# Polivator.net
KiCad netlist of a schematic drawn in EAGLE
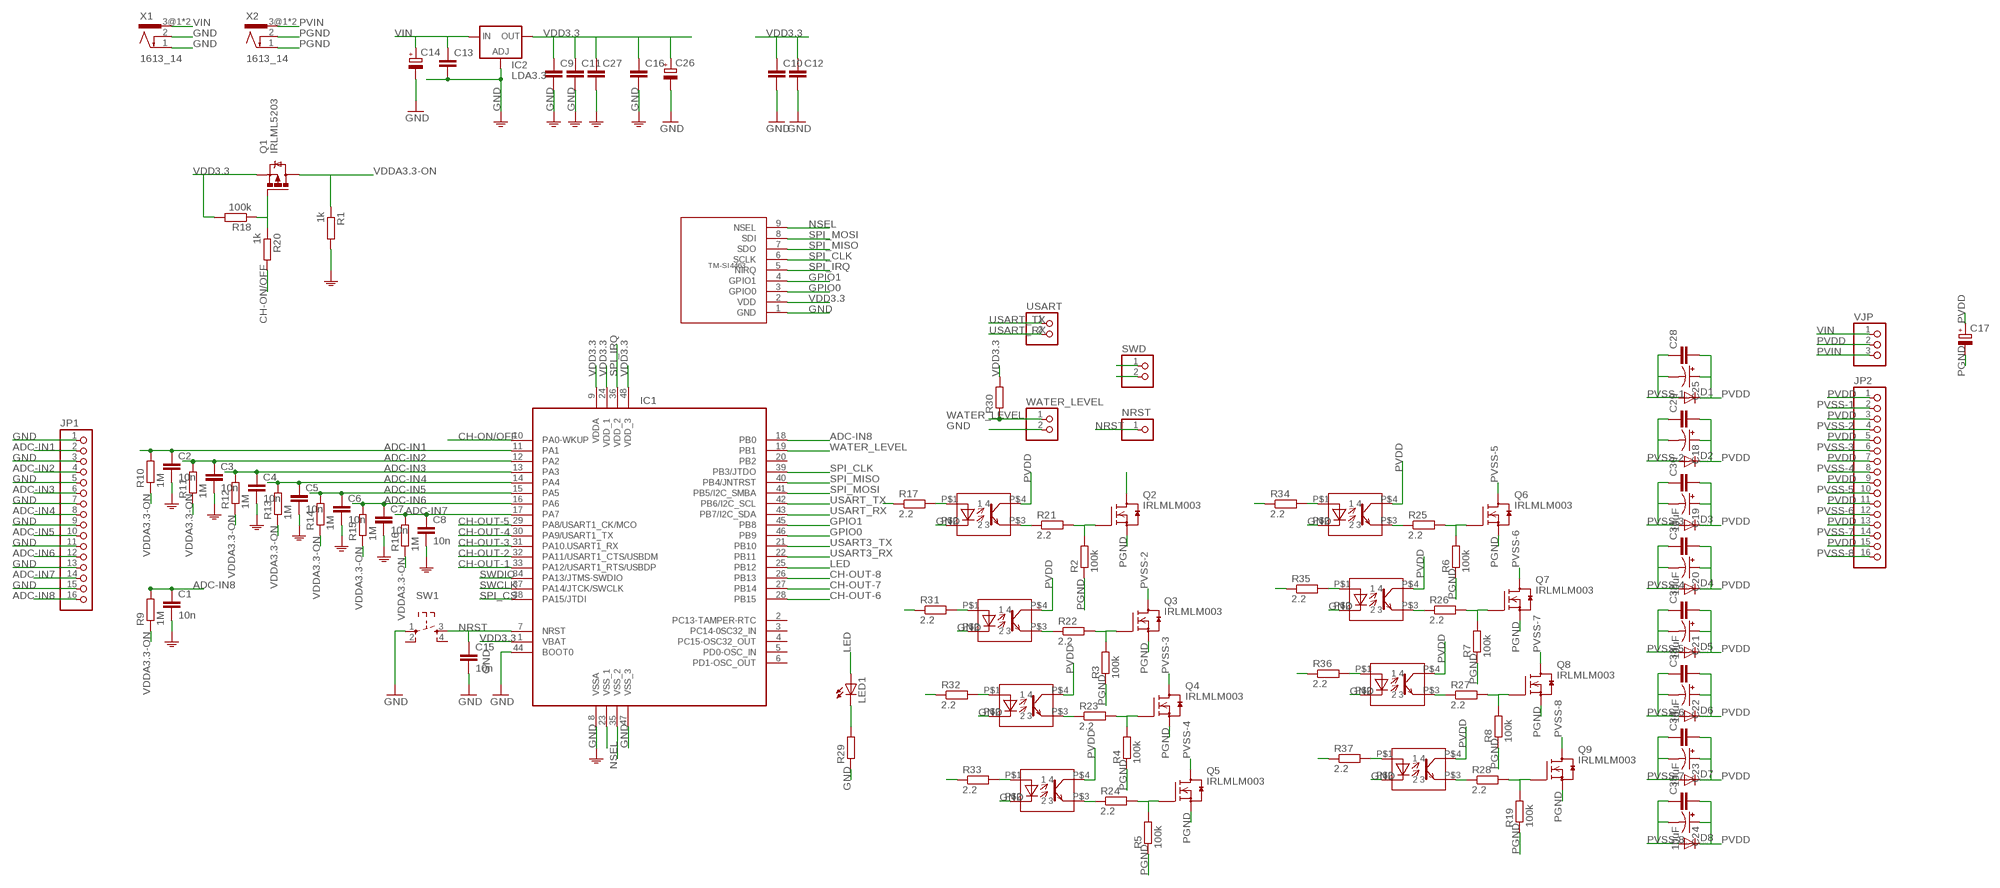
[diagram p0: schematic, sheet 1]

(export (version "E")
  (design (tool "Eeschema 10.0.6"))
  (components
    (comp (ref "C1")
      (value "10n")
      (footprint "eagle-import:C0805")
      (libsource (lib "eagle-import") (part "C-EUC0805"))
    )
    (comp (ref "C2")
      (value "10n")
      (footprint "eagle-import:C0805")
      (libsource (lib "eagle-import") (part "C-EUC0805"))
    )
    (comp (ref "C3")
      (value "10n")
      (footprint "eagle-import:C0805")
      (libsource (lib "eagle-import") (part "C-EUC0805"))
    )
    (comp (ref "C4")
      (value "10n")
      (footprint "eagle-import:C0805")
      (libsource (lib "eagle-import") (part "C-EUC0805"))
    )
    (comp (ref "C5")
      (value "10n")
      (footprint "eagle-import:C0805")
      (libsource (lib "eagle-import") (part "C-EUC0805"))
    )
    (comp (ref "C6")
      (value "10n")
      (footprint "eagle-import:C0805")
      (libsource (lib "eagle-import") (part "C-EUC0805"))
    )
    (comp (ref "C7")
      (value "10n")
      (footprint "eagle-import:C0805")
      (libsource (lib "eagle-import") (part "C-EUC0805"))
    )
    (comp (ref "C8")
      (value "10n")
      (footprint "eagle-import:C0805")
      (libsource (lib "eagle-import") (part "C-EUC0805"))
    )
    (comp (ref "C9")
      (value "C-EUC3216")
      (footprint "eagle-import:C3216")
      (libsource (lib "eagle-import") (part "C-EUC3216"))
    )
    (comp (ref "C10")
      (value "C-EUC3216")
      (footprint "eagle-import:C3216")
      (libsource (lib "eagle-import") (part "C-EUC3216"))
    )
    (comp (ref "C11")
      (value "C-EUC0805")
      (footprint "eagle-import:C0805")
      (libsource (lib "eagle-import") (part "C-EUC0805"))
    )
    (comp (ref "C12")
      (value "C-EUC0805")
      (footprint "eagle-import:C0805")
      (libsource (lib "eagle-import") (part "C-EUC0805"))
    )
    (comp (ref "C13")
      (value "C-EUC1808")
      (footprint "eagle-import:C1808")
      (libsource (lib "eagle-import") (part "C-EUC1808"))
    )
    (comp (ref "C14")
      (value "CPOL-EUE2.5-5")
      (footprint "eagle-import:E2,5-5")
      (libsource (lib "eagle-import") (part "CPOL-EUE2.5-5"))
    )
    (comp (ref "C15")
      (value "10n")
      (footprint "eagle-import:C0805")
      (libsource (lib "eagle-import") (part "C-EUC0805"))
    )
    (comp (ref "C16")
      (value "C-EUC0805")
      (footprint "eagle-import:C0805")
      (libsource (lib "eagle-import") (part "C-EUC0805"))
    )
    (comp (ref "C17")
      (value "CPOL-EUE2.5-6")
      (footprint "eagle-import:E2,5-6")
      (libsource (lib "eagle-import") (part "CPOL-EUE2.5-6"))
    )
    (comp (ref "C18")
      (value "CAP_POL1206")
      (footprint "eagle-import:EIA3216")
      (libsource (lib "eagle-import") (part "CAP_POL1206"))
    )
    (comp (ref "C19")
      (value "10uF")
      (footprint "eagle-import:EIA3216")
      (libsource (lib "eagle-import") (part "10UF-16V-10%(TANT)"))
    )
    (comp (ref "C20")
      (value "10uF")
      (footprint "eagle-import:EIA3216")
      (libsource (lib "eagle-import") (part "10UF-16V-10%(TANT)"))
    )
    (comp (ref "C21")
      (value "10uF")
      (footprint "eagle-import:EIA3216")
      (libsource (lib "eagle-import") (part "10UF-16V-10%(TANT)"))
    )
    (comp (ref "C22")
      (value "10uF")
      (footprint "eagle-import:EIA3216")
      (libsource (lib "eagle-import") (part "10UF-16V-10%(TANT)"))
    )
    (comp (ref "C23")
      (value "10uF")
      (footprint "eagle-import:EIA3216")
      (libsource (lib "eagle-import") (part "10UF-16V-10%(TANT)"))
    )
    (comp (ref "C24")
      (value "10uF")
      (footprint "eagle-import:EIA3216")
      (libsource (lib "eagle-import") (part "10UF-16V-10%(TANT)"))
    )
    (comp (ref "C25")
      (value "CAP_POL1206")
      (footprint "eagle-import:EIA3216")
      (libsource (lib "eagle-import") (part "CAP_POL1206"))
    )
    (comp (ref "C26")
      (value "CPOL-EUE2.5-5")
      (footprint "eagle-import:E2,5-5")
      (libsource (lib "eagle-import") (part "CPOL-EUE2.5-5"))
    )
    (comp (ref "C27")
      (value "C-EUC0805")
      (footprint "eagle-import:C0805")
      (libsource (lib "eagle-import") (part "C-EUC0805"))
    )
    (comp (ref "C28")
      (value "C-EUC0805")
      (footprint "eagle-import:C0805")
      (libsource (lib "eagle-import") (part "C-EUC0805"))
    )
    (comp (ref "C29")
      (value "C-EUC0805")
      (footprint "eagle-import:C0805")
      (libsource (lib "eagle-import") (part "C-EUC0805"))
    )
    (comp (ref "C30")
      (value "C-EUC0805")
      (footprint "eagle-import:C0805")
      (libsource (lib "eagle-import") (part "C-EUC0805"))
    )
    (comp (ref "C31")
      (value "C-EUC0805")
      (footprint "eagle-import:C0805")
      (libsource (lib "eagle-import") (part "C-EUC0805"))
    )
    (comp (ref "C32")
      (value "C-EUC0805")
      (footprint "eagle-import:C0805")
      (libsource (lib "eagle-import") (part "C-EUC0805"))
    )
    (comp (ref "C33")
      (value "C-EUC0805")
      (footprint "eagle-import:C0805")
      (libsource (lib "eagle-import") (part "C-EUC0805"))
    )
    (comp (ref "C34")
      (value "C-EUC0805")
      (footprint "eagle-import:C0805")
      (libsource (lib "eagle-import") (part "C-EUC0805"))
    )
    (comp (ref "C35")
      (value "C-EUC0805")
      (footprint "eagle-import:C0805")
      (libsource (lib "eagle-import") (part "C-EUC0805"))
    )
    (comp (ref "D1")
      (value "DIODE-SOD80C")
      (footprint "eagle-import:SOD80C")
      (libsource (lib "eagle-import") (part "DIODE-SOD80C"))
    )
    (comp (ref "D2")
      (value "DIODE-SOD80C")
      (footprint "eagle-import:SOD80C")
      (libsource (lib "eagle-import") (part "DIODE-SOD80C"))
    )
    (comp (ref "D3")
      (value "DIODE-SOD80C")
      (footprint "eagle-import:SOD80C")
      (libsource (lib "eagle-import") (part "DIODE-SOD80C"))
    )
    (comp (ref "D4")
      (value "DIODE-SOD80C")
      (footprint "eagle-import:SOD80C")
      (libsource (lib "eagle-import") (part "DIODE-SOD80C"))
    )
    (comp (ref "D5")
      (value "DIODE-SOD80C")
      (footprint "eagle-import:SOD80C")
      (libsource (lib "eagle-import") (part "DIODE-SOD80C"))
    )
    (comp (ref "D6")
      (value "DIODE-SOD80C")
      (footprint "eagle-import:SOD80C")
      (libsource (lib "eagle-import") (part "DIODE-SOD80C"))
    )
    (comp (ref "D7")
      (value "DIODE-SOD80C")
      (footprint "eagle-import:SOD80C")
      (libsource (lib "eagle-import") (part "DIODE-SOD80C"))
    )
    (comp (ref "D8")
      (value "DIODE-SOD80C")
      (footprint "eagle-import:SOD80C")
      (libsource (lib "eagle-import") (part "DIODE-SOD80C"))
    )
    (comp (ref "IC1")
      (value "IC_UC_STM32")
      (footprint "eagle-import:LQFP48")
      (libsource (lib "eagle-import") (part "IC_UC_STM32"))
    )
    (comp (ref "IC2")
      (value "LDA3.3")
      (footprint "eagle-import:SOT223")
      (libsource (lib "eagle-import") (part "LD117A?STR"))
    )
    (comp (ref "JP1")
      (value "PINHD-1X16")
      (footprint "eagle-import:1X16")
      (libsource (lib "eagle-import") (part "PINHD-1X16"))
    )
    (comp (ref "JP2")
      (value "PINHD-1X16")
      (footprint "eagle-import:1X16")
      (libsource (lib "eagle-import") (part "PINHD-1X16"))
    )
    (comp (ref "LED1")
      (value "LEDCHIPLED_0805")
      (footprint "eagle-import:CHIPLED_0805")
      (libsource (lib "eagle-import") (part "LEDCHIPLED_0805"))
    )
    (comp (ref "NRST")
      (value "PINHD-1X1")
      (footprint "eagle-import:1X01")
      (libsource (lib "eagle-import") (part "PINHD-1X1"))
    )
    (comp (ref "Q1")
      (value "IRLML5203")
      (footprint "eagle-import:MICRO3")
      (libsource (lib "eagle-import") (part "IRLML5203"))
    )
    (comp (ref "Q2")
      (value "IRLMLM003")
      (footprint "eagle-import:SOT23")
      (libsource (lib "eagle-import") (part "BSS138"))
    )
    (comp (ref "Q3")
      (value "IRLMLM003")
      (footprint "eagle-import:SOT23")
      (libsource (lib "eagle-import") (part "BSS138"))
    )
    (comp (ref "Q4")
      (value "IRLMLM003")
      (footprint "eagle-import:SOT23")
      (libsource (lib "eagle-import") (part "BSS138"))
    )
    (comp (ref "Q5")
      (value "IRLMLM003")
      (footprint "eagle-import:SOT23")
      (libsource (lib "eagle-import") (part "BSS138"))
    )
    (comp (ref "Q6")
      (value "IRLMLM003")
      (footprint "eagle-import:SOT23")
      (libsource (lib "eagle-import") (part "BSS138"))
    )
    (comp (ref "Q7")
      (value "IRLMLM003")
      (footprint "eagle-import:SOT23")
      (libsource (lib "eagle-import") (part "BSS138"))
    )
    (comp (ref "Q8")
      (value "IRLMLM003")
      (footprint "eagle-import:SOT23")
      (libsource (lib "eagle-import") (part "BSS138"))
    )
    (comp (ref "Q9")
      (value "IRLMLM003")
      (footprint "eagle-import:SOT23")
      (libsource (lib "eagle-import") (part "BSS138"))
    )
    (comp (ref "R1")
      (value "1k")
      (footprint "eagle-import:R0805")
      (libsource (lib "eagle-import") (part "R-EU_R0805"))
    )
    (comp (ref "R2")
      (value "100k")
      (footprint "eagle-import:R0805")
      (libsource (lib "eagle-import") (part "R-EU_R0805"))
    )
    (comp (ref "R3")
      (value "100k")
      (footprint "eagle-import:R0805")
      (libsource (lib "eagle-import") (part "R-EU_R0805"))
    )
    (comp (ref "R4")
      (value "100k")
      (footprint "eagle-import:R0805")
      (libsource (lib "eagle-import") (part "R-EU_R0805"))
    )
    (comp (ref "R5")
      (value "100k")
      (footprint "eagle-import:R0805")
      (libsource (lib "eagle-import") (part "R-EU_R0805"))
    )
    (comp (ref "R6")
      (value "100k")
      (footprint "eagle-import:R0805")
      (libsource (lib "eagle-import") (part "R-EU_R0805"))
    )
    (comp (ref "R7")
      (value "100k")
      (footprint "eagle-import:R0805")
      (libsource (lib "eagle-import") (part "R-EU_R0805"))
    )
    (comp (ref "R8")
      (value "100k")
      (footprint "eagle-import:R0805")
      (libsource (lib "eagle-import") (part "R-EU_R0805"))
    )
    (comp (ref "R9")
      (value "1M")
      (footprint "eagle-import:R0805")
      (libsource (lib "eagle-import") (part "R-EU_R0805"))
    )
    (comp (ref "R10")
      (value "1M")
      (footprint "eagle-import:R0805")
      (libsource (lib "eagle-import") (part "R-EU_R0805"))
    )
    (comp (ref "R11")
      (value "1M")
      (footprint "eagle-import:R0805")
      (libsource (lib "eagle-import") (part "R-EU_R0805"))
    )
    (comp (ref "R12")
      (value "1M")
      (footprint "eagle-import:R0805")
      (libsource (lib "eagle-import") (part "R-EU_R0805"))
    )
    (comp (ref "R13")
      (value "1M")
      (footprint "eagle-import:R0805")
      (libsource (lib "eagle-import") (part "R-EU_R0805"))
    )
    (comp (ref "R14")
      (value "1M")
      (footprint "eagle-import:R0805")
      (libsource (lib "eagle-import") (part "R-EU_R0805"))
    )
    (comp (ref "R15")
      (value "1M")
      (footprint "eagle-import:R0805")
      (libsource (lib "eagle-import") (part "R-EU_R0805"))
    )
    (comp (ref "R16")
      (value "1M")
      (footprint "eagle-import:R0805")
      (libsource (lib "eagle-import") (part "R-EU_R0805"))
    )
    (comp (ref "R17")
      (value "2.2")
      (footprint "eagle-import:R0805")
      (libsource (lib "eagle-import") (part "R-EU_R0805"))
    )
    (comp (ref "R18")
      (value "100k")
      (footprint "eagle-import:R0805")
      (libsource (lib "eagle-import") (part "R-EU_R0805"))
    )
    (comp (ref "R19")
      (value "100k")
      (footprint "eagle-import:R0805")
      (libsource (lib "eagle-import") (part "R-EU_R0805"))
    )
    (comp (ref "R20")
      (value "1k")
      (footprint "eagle-import:R0805")
      (libsource (lib "eagle-import") (part "R-EU_R0805"))
    )
    (comp (ref "R21")
      (value "2.2")
      (footprint "eagle-import:R0805")
      (libsource (lib "eagle-import") (part "R-EU_R0805"))
    )
    (comp (ref "R22")
      (value "2.2")
      (footprint "eagle-import:R0805")
      (libsource (lib "eagle-import") (part "R-EU_R0805"))
    )
    (comp (ref "R23")
      (value "2.2")
      (footprint "eagle-import:R0805")
      (libsource (lib "eagle-import") (part "R-EU_R0805"))
    )
    (comp (ref "R24")
      (value "2.2")
      (footprint "eagle-import:R0805")
      (libsource (lib "eagle-import") (part "R-EU_R0805"))
    )
    (comp (ref "R25")
      (value "2.2")
      (footprint "eagle-import:R0805")
      (libsource (lib "eagle-import") (part "R-EU_R0805"))
    )
    (comp (ref "R26")
      (value "2.2")
      (footprint "eagle-import:R0805")
      (libsource (lib "eagle-import") (part "R-EU_R0805"))
    )
    (comp (ref "R27")
      (value "2.2")
      (footprint "eagle-import:R0805")
      (libsource (lib "eagle-import") (part "R-EU_R0805"))
    )
    (comp (ref "R28")
      (value "2.2")
      (footprint "eagle-import:R0805")
      (libsource (lib "eagle-import") (part "R-EU_R0805"))
    )
    (comp (ref "R29")
      (value "R-EU_R0805")
      (footprint "eagle-import:R0805")
      (libsource (lib "eagle-import") (part "R-EU_R0805"))
    )
    (comp (ref "R30")
      (value "R-EU_R0805")
      (footprint "eagle-import:R0805")
      (libsource (lib "eagle-import") (part "R-EU_R0805"))
    )
    (comp (ref "R31")
      (value "2.2")
      (footprint "eagle-import:R0805")
      (libsource (lib "eagle-import") (part "R-EU_R0805"))
    )
    (comp (ref "R32")
      (value "2.2")
      (footprint "eagle-import:R0805")
      (libsource (lib "eagle-import") (part "R-EU_R0805"))
    )
    (comp (ref "R33")
      (value "2.2")
      (footprint "eagle-import:R0805")
      (libsource (lib "eagle-import") (part "R-EU_R0805"))
    )
    (comp (ref "R34")
      (value "2.2")
      (footprint "eagle-import:R0805")
      (libsource (lib "eagle-import") (part "R-EU_R0805"))
    )
    (comp (ref "R35")
      (value "2.2")
      (footprint "eagle-import:R0805")
      (libsource (lib "eagle-import") (part "R-EU_R0805"))
    )
    (comp (ref "R36")
      (value "2.2")
      (footprint "eagle-import:R0805")
      (libsource (lib "eagle-import") (part "R-EU_R0805"))
    )
    (comp (ref "R37")
      (value "2.2")
      (footprint "eagle-import:R0805")
      (libsource (lib "eagle-import") (part "R-EU_R0805"))
    )
    (comp (ref "SW1")
      (value "SW_TACT_4P")
      (footprint "eagle-import:SW_TACT_SMALL")
      (libsource (lib "eagle-import") (part "SW_TACT_4P"))
    )
    (comp (ref "SWD")
      (value "PINHD-1X2")
      (footprint "eagle-import:1X02")
      (libsource (lib "eagle-import") (part "PINHD-1X2"))
    )
    (comp (ref "U$8")
      (value "TM-SI4463")
      (footprint "eagle-import:TM-SI4463-SMD")
      (libsource (lib "eagle-import") (part "TM-SI4463"))
    )
    (comp (ref "U$10")
      (value "PC817-SMD")
      (footprint "eagle-import:PC817-SMD")
      (libsource (lib "eagle-import") (part "PC817-SMD"))
    )
    (comp (ref "U$11")
      (value "PC817-SMD")
      (footprint "eagle-import:PC817-SMD")
      (libsource (lib "eagle-import") (part "PC817-SMD"))
    )
    (comp (ref "U$13")
      (value "PC817-SMD")
      (footprint "eagle-import:PC817-SMD")
      (libsource (lib "eagle-import") (part "PC817-SMD"))
    )
    (comp (ref "U$16")
      (value "PC817-SMD")
      (footprint "eagle-import:PC817-SMD")
      (libsource (lib "eagle-import") (part "PC817-SMD"))
    )
    (comp (ref "U$18")
      (value "PC817-SMD")
      (footprint "eagle-import:PC817-SMD")
      (libsource (lib "eagle-import") (part "PC817-SMD"))
    )
    (comp (ref "U$20")
      (value "PC817-SMD")
      (footprint "eagle-import:PC817-SMD")
      (libsource (lib "eagle-import") (part "PC817-SMD"))
    )
    (comp (ref "U$23")
      (value "PC817-SMD")
      (footprint "eagle-import:PC817-SMD")
      (libsource (lib "eagle-import") (part "PC817-SMD"))
    )
    (comp (ref "U$24")
      (value "PC817-SMD")
      (footprint "eagle-import:PC817-SMD")
      (libsource (lib "eagle-import") (part "PC817-SMD"))
    )
    (comp (ref "USART")
      (value "PINHD-1X2")
      (footprint "eagle-import:1X02")
      (libsource (lib "eagle-import") (part "PINHD-1X2"))
    )
    (comp (ref "VJP")
      (value "PINHD-1X3")
      (footprint "eagle-import:1X03")
      (libsource (lib "eagle-import") (part "PINHD-1X3"))
    )
    (comp (ref "WATER_LEVEL")
      (value "PINHD-1X2")
      (footprint "eagle-import:1X02")
      (libsource (lib "eagle-import") (part "PINHD-1X2"))
    )
    (comp (ref "X1")
      (value "1613_14")
      (footprint "eagle-import:1613_14")
      (fields (field (name "MF") "LUMBERG") (field (name "MPN") "1613 14"))
      (libsource (lib "eagle-import") (part "1613_14"))
    )
    (comp (ref "X2")
      (value "1613_14")
      (footprint "eagle-import:1613_14")
      (fields (field (name "MF") "LUMBERG") (field (name "MPN") "1613 14"))
      (libsource (lib "eagle-import") (part "1613_14"))
    )
  )
  (nets
    (net (code "1") (name "/ADC-IN1") (class "Default")
      (node (ref "C2") (pin "1") (pinfunction "1_1") (pintype "passive"))
      (node (ref "IC1") (pin "11") (pinfunction "PA1_11") (pintype "bidirectional"))
      (node (ref "JP1") (pin "2") (pinfunction "2_2") (pintype "passive"))
      (node (ref "R10") (pin "2") (pinfunction "2_2") (pintype "passive"))
    )
    (net (code "2") (name "/ADC-IN2") (class "Default")
      (node (ref "C3") (pin "1") (pinfunction "1_1") (pintype "passive"))
      (node (ref "IC1") (pin "12") (pinfunction "PA2_12") (pintype "bidirectional"))
      (node (ref "JP1") (pin "4") (pinfunction "4_4") (pintype "passive"))
      (node (ref "R11") (pin "2") (pinfunction "2_2") (pintype "passive"))
    )
    (net (code "3") (name "/ADC-IN3") (class "Default")
      (node (ref "C4") (pin "1") (pinfunction "1_1") (pintype "passive"))
      (node (ref "IC1") (pin "13") (pinfunction "PA3_13") (pintype "bidirectional"))
      (node (ref "JP1") (pin "6") (pinfunction "6_6") (pintype "passive"))
      (node (ref "R12") (pin "2") (pinfunction "2_2") (pintype "passive"))
    )
    (net (code "4") (name "/ADC-IN4") (class "Default")
      (node (ref "C5") (pin "1") (pinfunction "1_1") (pintype "passive"))
      (node (ref "IC1") (pin "14") (pinfunction "PA4_14") (pintype "bidirectional"))
      (node (ref "JP1") (pin "8") (pinfunction "8_8") (pintype "passive"))
      (node (ref "R13") (pin "2") (pinfunction "2_2") (pintype "passive"))
    )
    (net (code "5") (name "/ADC-IN5") (class "Default")
      (node (ref "C6") (pin "1") (pinfunction "1_1") (pintype "passive"))
      (node (ref "IC1") (pin "15") (pinfunction "PA5_15") (pintype "bidirectional"))
      (node (ref "JP1") (pin "10") (pinfunction "10_10") (pintype "passive"))
      (node (ref "R14") (pin "2") (pinfunction "2_2") (pintype "passive"))
    )
    (net (code "6") (name "/ADC-IN6") (class "Default")
      (node (ref "C7") (pin "1") (pinfunction "1_1") (pintype "passive"))
      (node (ref "IC1") (pin "16") (pinfunction "PA6_16") (pintype "bidirectional"))
      (node (ref "JP1") (pin "12") (pinfunction "12_12") (pintype "passive"))
      (node (ref "R15") (pin "2") (pinfunction "2_2") (pintype "passive"))
    )
    (net (code "7") (name "/ADC-IN7") (class "Default")
      (node (ref "C8") (pin "1") (pinfunction "1_1") (pintype "passive"))
      (node (ref "IC1") (pin "17") (pinfunction "PA7_17") (pintype "bidirectional"))
      (node (ref "JP1") (pin "14") (pinfunction "14_14") (pintype "passive"))
      (node (ref "R16") (pin "2") (pinfunction "2_2") (pintype "passive"))
    )
    (net (code "8") (name "/ADC-IN8") (class "Default")
      (node (ref "C1") (pin "1") (pinfunction "1_1") (pintype "passive"))
      (node (ref "IC1") (pin "18") (pinfunction "PB0_18") (pintype "bidirectional"))
      (node (ref "JP1") (pin "16") (pinfunction "16_16") (pintype "passive"))
      (node (ref "R9") (pin "2") (pinfunction "2_2") (pintype "passive"))
    )
    (net (code "9") (name "/CH-ON{slash}OFF") (class "Default")
      (node (ref "IC1") (pin "10") (pinfunction "PA0-WKUP_10") (pintype "bidirectional"))
      (node (ref "R20") (pin "2") (pinfunction "2_2") (pintype "passive"))
    )
    (net (code "10") (name "/CH-OUT-1") (class "Default")
      (node (ref "IC1") (pin "33") (pinfunction "PA12/USART1_RTS/USBDP_33") (pintype "bidirectional"))
      (node (ref "R17") (pin "1") (pinfunction "1_1") (pintype "passive"))
    )
    (net (code "11") (name "/CH-OUT-2") (class "Default")
      (node (ref "IC1") (pin "32") (pinfunction "PA11/USART1_CTS/USBDM_32") (pintype "bidirectional"))
      (node (ref "R31") (pin "1") (pinfunction "1_1") (pintype "passive"))
    )
    (net (code "12") (name "/CH-OUT-3") (class "Default")
      (node (ref "IC1") (pin "31") (pinfunction "PA10.USART1_RX_31") (pintype "bidirectional"))
      (node (ref "R32") (pin "1") (pinfunction "1_1") (pintype "passive"))
    )
    (net (code "13") (name "/CH-OUT-4") (class "Default")
      (node (ref "IC1") (pin "30") (pinfunction "PA9/USART1_TX_30") (pintype "bidirectional"))
      (node (ref "R33") (pin "1") (pinfunction "1_1") (pintype "passive"))
    )
    (net (code "14") (name "/CH-OUT-5") (class "Default")
      (node (ref "IC1") (pin "29") (pinfunction "PA8/USART1_CK/MCO_29") (pintype "bidirectional"))
      (node (ref "R34") (pin "1") (pinfunction "1_1") (pintype "passive"))
    )
    (net (code "15") (name "/CH-OUT-6") (class "Default")
      (node (ref "IC1") (pin "28") (pinfunction "PB15_28") (pintype "bidirectional"))
      (node (ref "R35") (pin "1") (pinfunction "1_1") (pintype "passive"))
    )
    (net (code "16") (name "/CH-OUT-7") (class "Default")
      (node (ref "IC1") (pin "27") (pinfunction "PB14_27") (pintype "bidirectional"))
      (node (ref "R36") (pin "1") (pinfunction "1_1") (pintype "passive"))
    )
    (net (code "17") (name "/CH-OUT-8") (class "Default")
      (node (ref "IC1") (pin "26") (pinfunction "PB13_26") (pintype "bidirectional"))
      (node (ref "R37") (pin "1") (pinfunction "1_1") (pintype "passive"))
    )
    (net (code "18") (name "/GPIO0") (class "Default")
      (node (ref "IC1") (pin "46") (pinfunction "PB9_46") (pintype "bidirectional"))
      (node (ref "U$8") (pin "3") (pinfunction "GPIO0_3") (pintype "bidirectional"))
    )
    (net (code "19") (name "/GPIO1") (class "Default")
      (node (ref "IC1") (pin "45") (pinfunction "PB8_45") (pintype "bidirectional"))
      (node (ref "U$8") (pin "4") (pinfunction "GPIO1_4") (pintype "bidirectional"))
    )
    (net (code "20") (name "/LED") (class "Default")
      (node (ref "IC1") (pin "25") (pinfunction "PB12_25") (pintype "bidirectional"))
      (node (ref "LED1") (pin "A") (pinfunction "A_A") (pintype "passive"))
    )
    (net (code "21") (name "/NRST") (class "Default")
      (node (ref "C15") (pin "1") (pinfunction "1_1") (pintype "passive"))
      (node (ref "IC1") (pin "7") (pinfunction "NRST_7") (pintype "bidirectional"))
      (node (ref "NRST") (pin "1") (pinfunction "1_1") (pintype "passive"))
      (node (ref "SW1") (pin "3") (pinfunction "3_3") (pintype "passive"))
    )
    (net (code "22") (name "/NSEL") (class "Default")
      (node (ref "IC1") (pin "35") (pinfunction "VSS_2_35") (pintype "power_in"))
      (node (ref "U$8") (pin "9") (pinfunction "NSEL_9") (pintype "bidirectional"))
    )
    (net (code "23") (name "/PGND") (class "Default")
      (node (ref "C17") (pin "-") (pinfunction "-_-") (pintype "passive"))
      (node (ref "Q2") (pin "2") (pinfunction "S_2") (pintype "passive"))
      (node (ref "Q3") (pin "2") (pinfunction "S_2") (pintype "passive"))
      (node (ref "Q4") (pin "2") (pinfunction "S_2") (pintype "passive"))
      (node (ref "Q5") (pin "2") (pinfunction "S_2") (pintype "passive"))
      (node (ref "Q6") (pin "2") (pinfunction "S_2") (pintype "passive"))
      (node (ref "Q7") (pin "2") (pinfunction "S_2") (pintype "passive"))
      (node (ref "Q8") (pin "2") (pinfunction "S_2") (pintype "passive"))
      (node (ref "Q9") (pin "2") (pinfunction "S_2") (pintype "passive"))
      (node (ref "R19") (pin "1") (pinfunction "1_1") (pintype "passive"))
      (node (ref "R2") (pin "1") (pinfunction "1_1") (pintype "passive"))
      (node (ref "R3") (pin "1") (pinfunction "1_1") (pintype "passive"))
      (node (ref "R4") (pin "1") (pinfunction "1_1") (pintype "passive"))
      (node (ref "R5") (pin "1") (pinfunction "1_1") (pintype "passive"))
      (node (ref "R6") (pin "1") (pinfunction "1_1") (pintype "passive"))
      (node (ref "R7") (pin "1") (pinfunction "1_1") (pintype "passive"))
      (node (ref "R8") (pin "1") (pinfunction "1_1") (pintype "passive"))
      (node (ref "X2") (pin "1") (pinfunction "1_1") (pintype "passive"))
      (node (ref "X2") (pin "2") (pinfunction "2_2") (pintype "passive"))
    )
    (net (code "24") (name "/PVDD") (class "Default")
      (node (ref "C17") (pin "+") (pinfunction "+_+") (pintype "passive"))
      (node (ref "C18") (pin "A") (pinfunction "+_A") (pintype "passive"))
      (node (ref "C19") (pin "A") (pinfunction "+_A") (pintype "passive"))
      (node (ref "C20") (pin "A") (pinfunction "+_A") (pintype "passive"))
      (node (ref "C21") (pin "A") (pinfunction "+_A") (pintype "passive"))
      (node (ref "C22") (pin "A") (pinfunction "+_A") (pintype "passive"))
      (node (ref "C23") (pin "A") (pinfunction "+_A") (pintype "passive"))
      (node (ref "C24") (pin "A") (pinfunction "+_A") (pintype "passive"))
      (node (ref "C25") (pin "A") (pinfunction "+_A") (pintype "passive"))
      (node (ref "C28") (pin "2") (pinfunction "2_2") (pintype "passive"))
      (node (ref "C29") (pin "2") (pinfunction "2_2") (pintype "passive"))
      (node (ref "C30") (pin "2") (pinfunction "2_2") (pintype "passive"))
      (node (ref "C31") (pin "2") (pinfunction "2_2") (pintype "passive"))
      (node (ref "C32") (pin "2") (pinfunction "2_2") (pintype "passive"))
      (node (ref "C33") (pin "2") (pinfunction "2_2") (pintype "passive"))
      (node (ref "C34") (pin "2") (pinfunction "2_2") (pintype "passive"))
      (node (ref "C35") (pin "2") (pinfunction "2_2") (pintype "passive"))
      (node (ref "D1") (pin "C") (pinfunction "C_C") (pintype "passive"))
      (node (ref "D2") (pin "C") (pinfunction "C_C") (pintype "passive"))
      (node (ref "D3") (pin "C") (pinfunction "C_C") (pintype "passive"))
      (node (ref "D4") (pin "C") (pinfunction "C_C") (pintype "passive"))
      (node (ref "D5") (pin "C") (pinfunction "C_C") (pintype "passive"))
      (node (ref "D6") (pin "C") (pinfunction "C_C") (pintype "passive"))
      (node (ref "D7") (pin "C") (pinfunction "C_C") (pintype "passive"))
      (node (ref "D8") (pin "C") (pinfunction "C_C") (pintype "passive"))
      (node (ref "JP2") (pin "1") (pinfunction "1_1") (pintype "passive"))
      (node (ref "JP2") (pin "11") (pinfunction "11_11") (pintype "passive"))
      (node (ref "JP2") (pin "13") (pinfunction "13_13") (pintype "passive"))
      (node (ref "JP2") (pin "15") (pinfunction "15_15") (pintype "passive"))
      (node (ref "JP2") (pin "3") (pinfunction "3_3") (pintype "passive"))
      (node (ref "JP2") (pin "5") (pinfunction "5_5") (pintype "passive"))
      (node (ref "JP2") (pin "7") (pinfunction "7_7") (pintype "passive"))
      (node (ref "JP2") (pin "9") (pinfunction "9_9") (pintype "passive"))
      (node (ref "U$10") (pin "P$4") (pinfunction "4_P$4") (pintype "bidirectional"))
      (node (ref "U$11") (pin "P$4") (pinfunction "4_P$4") (pintype "bidirectional"))
      (node (ref "U$13") (pin "P$4") (pinfunction "4_P$4") (pintype "bidirectional"))
      (node (ref "U$16") (pin "P$4") (pinfunction "4_P$4") (pintype "bidirectional"))
      (node (ref "U$18") (pin "P$4") (pinfunction "4_P$4") (pintype "bidirectional"))
      (node (ref "U$20") (pin "P$4") (pinfunction "4_P$4") (pintype "bidirectional"))
      (node (ref "U$23") (pin "P$4") (pinfunction "4_P$4") (pintype "bidirectional"))
      (node (ref "U$24") (pin "P$4") (pinfunction "4_P$4") (pintype "bidirectional"))
      (node (ref "VJP") (pin "2") (pinfunction "2_2") (pintype "passive"))
    )
    (net (code "25") (name "/PVIN") (class "Default")
      (node (ref "VJP") (pin "3") (pinfunction "3_3") (pintype "passive"))
      (node (ref "X2") (pin "3@1") (pinfunction "3_3@1") (pintype "passive"))
      (node (ref "X2") (pin "3@2") (pinfunction "3_3@2") (pintype "passive"))
    )
    (net (code "26") (name "/PVSS-1") (class "Default")
      (node (ref "C25") (pin "C") (pinfunction "-_C") (pintype "passive"))
      (node (ref "C28") (pin "1") (pinfunction "1_1") (pintype "passive"))
      (node (ref "D1") (pin "A") (pinfunction "A_A") (pintype "passive"))
      (node (ref "JP2") (pin "2") (pinfunction "2_2") (pintype "passive"))
      (node (ref "Q2") (pin "3") (pinfunction "D_3") (pintype "passive"))
    )
    (net (code "27") (name "/PVSS-2") (class "Default")
      (node (ref "C18") (pin "C") (pinfunction "-_C") (pintype "passive"))
      (node (ref "C29") (pin "1") (pinfunction "1_1") (pintype "passive"))
      (node (ref "D2") (pin "A") (pinfunction "A_A") (pintype "passive"))
      (node (ref "JP2") (pin "4") (pinfunction "4_4") (pintype "passive"))
      (node (ref "Q3") (pin "3") (pinfunction "D_3") (pintype "passive"))
    )
    (net (code "28") (name "/PVSS-3") (class "Default")
      (node (ref "C19") (pin "C") (pinfunction "-_C") (pintype "passive"))
      (node (ref "C30") (pin "1") (pinfunction "1_1") (pintype "passive"))
      (node (ref "D3") (pin "A") (pinfunction "A_A") (pintype "passive"))
      (node (ref "JP2") (pin "6") (pinfunction "6_6") (pintype "passive"))
      (node (ref "Q4") (pin "3") (pinfunction "D_3") (pintype "passive"))
    )
    (net (code "29") (name "/PVSS-4") (class "Default")
      (node (ref "C20") (pin "C") (pinfunction "-_C") (pintype "passive"))
      (node (ref "C31") (pin "1") (pinfunction "1_1") (pintype "passive"))
      (node (ref "D4") (pin "A") (pinfunction "A_A") (pintype "passive"))
      (node (ref "JP2") (pin "8") (pinfunction "8_8") (pintype "passive"))
      (node (ref "Q5") (pin "3") (pinfunction "D_3") (pintype "passive"))
    )
    (net (code "30") (name "/PVSS-5") (class "Default")
      (node (ref "C21") (pin "C") (pinfunction "-_C") (pintype "passive"))
      (node (ref "C32") (pin "1") (pinfunction "1_1") (pintype "passive"))
      (node (ref "D5") (pin "A") (pinfunction "A_A") (pintype "passive"))
      (node (ref "JP2") (pin "10") (pinfunction "10_10") (pintype "passive"))
      (node (ref "Q6") (pin "3") (pinfunction "D_3") (pintype "passive"))
    )
    (net (code "31") (name "/PVSS-6") (class "Default")
      (node (ref "C22") (pin "C") (pinfunction "-_C") (pintype "passive"))
      (node (ref "C33") (pin "1") (pinfunction "1_1") (pintype "passive"))
      (node (ref "D6") (pin "A") (pinfunction "A_A") (pintype "passive"))
      (node (ref "JP2") (pin "12") (pinfunction "12_12") (pintype "passive"))
      (node (ref "Q7") (pin "3") (pinfunction "D_3") (pintype "passive"))
    )
    (net (code "32") (name "/PVSS-7") (class "Default")
      (node (ref "C23") (pin "C") (pinfunction "-_C") (pintype "passive"))
      (node (ref "C34") (pin "1") (pinfunction "1_1") (pintype "passive"))
      (node (ref "D7") (pin "A") (pinfunction "A_A") (pintype "passive"))
      (node (ref "JP2") (pin "14") (pinfunction "14_14") (pintype "passive"))
      (node (ref "Q8") (pin "3") (pinfunction "D_3") (pintype "passive"))
    )
    (net (code "33") (name "/PVSS-8") (class "Default")
      (node (ref "C24") (pin "C") (pinfunction "-_C") (pintype "passive"))
      (node (ref "C35") (pin "1") (pinfunction "1_1") (pintype "passive"))
      (node (ref "D8") (pin "A") (pinfunction "A_A") (pintype "passive"))
      (node (ref "JP2") (pin "16") (pinfunction "16_16") (pintype "passive"))
      (node (ref "Q9") (pin "3") (pinfunction "D_3") (pintype "passive"))
    )
    (net (code "34") (name "/SPI_CLK") (class "Default")
      (node (ref "IC1") (pin "39") (pinfunction "PB3/JTDO_39") (pintype "bidirectional"))
      (node (ref "U$8") (pin "6") (pinfunction "SCLK_6") (pintype "bidirectional"))
    )
    (net (code "35") (name "/SPI_CS") (class "Default")
      (node (ref "IC1") (pin "38") (pinfunction "PA15/JTDI_38") (pintype "bidirectional"))
    )
    (net (code "36") (name "/SPI_IRQ") (class "Default")
      (node (ref "IC1") (pin "36") (pinfunction "VDD_2_36") (pintype "power_in"))
      (node (ref "U$8") (pin "5") (pinfunction "NIRQ_5") (pintype "bidirectional"))
    )
    (net (code "37") (name "/SPI_MISO") (class "Default")
      (node (ref "IC1") (pin "40") (pinfunction "PB4/JNTRST_40") (pintype "bidirectional"))
      (node (ref "U$8") (pin "7") (pinfunction "SDO_7") (pintype "bidirectional"))
    )
    (net (code "38") (name "/SPI_MOSI") (class "Default")
      (node (ref "IC1") (pin "41") (pinfunction "PB5/I2C_SMBA_41") (pintype "bidirectional"))
      (node (ref "U$8") (pin "8") (pinfunction "SDI_8") (pintype "bidirectional"))
    )
    (net (code "39") (name "/SWCLK") (class "Default")
      (node (ref "IC1") (pin "37") (pinfunction "PA14/JTCK/SWCLK_37") (pintype "bidirectional"))
      (node (ref "SWD") (pin "2") (pinfunction "2_2") (pintype "passive"))
    )
    (net (code "40") (name "/SWDIO") (class "Default")
      (node (ref "IC1") (pin "34") (pinfunction "PA13/JTMS-SWDIO_34") (pintype "bidirectional"))
      (node (ref "SWD") (pin "1") (pinfunction "1_1") (pintype "passive"))
    )
    (net (code "41") (name "/USART3_RX") (class "Default")
      (node (ref "IC1") (pin "22") (pinfunction "PB11_22") (pintype "bidirectional"))
    )
    (net (code "42") (name "/USART3_TX") (class "Default")
      (node (ref "IC1") (pin "21") (pinfunction "PB10_21") (pintype "bidirectional"))
    )
    (net (code "43") (name "/USART_RX") (class "Default")
      (node (ref "IC1") (pin "43") (pinfunction "PB7/I2C_SDA_43") (pintype "bidirectional"))
      (node (ref "USART") (pin "2") (pinfunction "2_2") (pintype "passive"))
    )
    (net (code "44") (name "/USART_TX") (class "Default")
      (node (ref "IC1") (pin "42") (pinfunction "PB6/I2C_SCL_42") (pintype "bidirectional"))
      (node (ref "USART") (pin "1") (pinfunction "1_1") (pintype "passive"))
    )
    (net (code "45") (name "/VDD3.3") (class "Default")
      (node (ref "C10") (pin "1") (pinfunction "1_1") (pintype "passive"))
      (node (ref "C11") (pin "1") (pinfunction "1_1") (pintype "passive"))
      (node (ref "C12") (pin "1") (pinfunction "1_1") (pintype "passive"))
      (node (ref "C16") (pin "1") (pinfunction "1_1") (pintype "passive"))
      (node (ref "C26") (pin "+") (pinfunction "+_+") (pintype "passive"))
      (node (ref "C27") (pin "1") (pinfunction "1_1") (pintype "passive"))
      (node (ref "C9") (pin "1") (pinfunction "1_1") (pintype "passive"))
      (node (ref "IC1") (pin "1") (pinfunction "VBAT_1") (pintype "bidirectional"))
      (node (ref "IC1") (pin "24") (pinfunction "VDD_1_24") (pintype "power_in"))
      (node (ref "IC1") (pin "48") (pinfunction "VDD_3_48") (pintype "power_in"))
      (node (ref "IC1") (pin "9") (pinfunction "VDDA_9") (pintype "power_in"))
      (node (ref "IC2") (pin "4") (pinfunction "OUT_4") (pintype "passive"))
      (node (ref "Q1") (pin "2") (pinfunction "S_2") (pintype "passive"))
      (node (ref "R18") (pin "2") (pinfunction "2_2") (pintype "passive"))
      (node (ref "R30") (pin "2") (pinfunction "2_2") (pintype "passive"))
      (node (ref "U$8") (pin "2") (pinfunction "VDD_2") (pintype "power_in"))
    )
    (net (code "46") (name "/VDDA3.3-ON") (class "Default")
      (node (ref "Q1") (pin "3") (pinfunction "D_3") (pintype "passive"))
      (node (ref "R1") (pin "1") (pinfunction "1_1") (pintype "passive"))
      (node (ref "R10") (pin "1") (pinfunction "1_1") (pintype "passive"))
      (node (ref "R11") (pin "1") (pinfunction "1_1") (pintype "passive"))
      (node (ref "R12") (pin "1") (pinfunction "1_1") (pintype "passive"))
      (node (ref "R13") (pin "1") (pinfunction "1_1") (pintype "passive"))
      (node (ref "R14") (pin "1") (pinfunction "1_1") (pintype "passive"))
      (node (ref "R15") (pin "1") (pinfunction "1_1") (pintype "passive"))
      (node (ref "R16") (pin "1") (pinfunction "1_1") (pintype "passive"))
      (node (ref "R9") (pin "1") (pinfunction "1_1") (pintype "passive"))
    )
    (net (code "47") (name "/VIN") (class "Default")
      (node (ref "C13") (pin "1") (pinfunction "1_1") (pintype "passive"))
      (node (ref "C14") (pin "+") (pinfunction "+_+") (pintype "passive"))
      (node (ref "IC2") (pin "3") (pinfunction "IN_3") (pintype "input"))
      (node (ref "VJP") (pin "1") (pinfunction "1_1") (pintype "passive"))
      (node (ref "X1") (pin "3@1") (pinfunction "3_3@1") (pintype "passive"))
      (node (ref "X1") (pin "3@2") (pinfunction "3_3@2") (pintype "passive"))
    )
    (net (code "48") (name "/WATER_LEVEL") (class "Default")
      (node (ref "IC1") (pin "19") (pinfunction "PB1_19") (pintype "bidirectional"))
      (node (ref "R30") (pin "1") (pinfunction "1_1") (pintype "passive"))
      (node (ref "WATER_LEVEL") (pin "1") (pinfunction "1_1") (pintype "passive"))
    )
    (net (code "49") (name "AGND") (class "Default")
      (node (ref "C1") (pin "2") (pinfunction "2_2") (pintype "passive"))
      (node (ref "C10") (pin "2") (pinfunction "2_2") (pintype "passive"))
      (node (ref "C11") (pin "2") (pinfunction "2_2") (pintype "passive"))
      (node (ref "C12") (pin "2") (pinfunction "2_2") (pintype "passive"))
      (node (ref "C13") (pin "2") (pinfunction "2_2") (pintype "passive"))
      (node (ref "C14") (pin "-") (pinfunction "-_-") (pintype "passive"))
      (node (ref "C15") (pin "2") (pinfunction "2_2") (pintype "passive"))
      (node (ref "C16") (pin "2") (pinfunction "2_2") (pintype "passive"))
      (node (ref "C2") (pin "2") (pinfunction "2_2") (pintype "passive"))
      (node (ref "C26") (pin "-") (pinfunction "-_-") (pintype "passive"))
      (node (ref "C27") (pin "2") (pinfunction "2_2") (pintype "passive"))
      (node (ref "C3") (pin "2") (pinfunction "2_2") (pintype "passive"))
      (node (ref "C4") (pin "2") (pinfunction "2_2") (pintype "passive"))
      (node (ref "C5") (pin "2") (pinfunction "2_2") (pintype "passive"))
      (node (ref "C6") (pin "2") (pinfunction "2_2") (pintype "passive"))
      (node (ref "C7") (pin "2") (pinfunction "2_2") (pintype "passive"))
      (node (ref "C8") (pin "2") (pinfunction "2_2") (pintype "passive"))
      (node (ref "C9") (pin "2") (pinfunction "2_2") (pintype "passive"))
      (node (ref "IC1") (pin "23") (pinfunction "VSS_1_23") (pintype "power_in"))
      (node (ref "IC1") (pin "44") (pinfunction "BOOT0_44") (pintype "bidirectional"))
      (node (ref "IC1") (pin "47") (pinfunction "VSS_3_47") (pintype "power_in"))
      (node (ref "IC1") (pin "8") (pinfunction "VSSA_8") (pintype "power_in"))
      (node (ref "IC2") (pin "1") (pinfunction "ADJ_1") (pintype "input"))
      (node (ref "JP1") (pin "1") (pinfunction "1_1") (pintype "passive"))
      (node (ref "JP1") (pin "11") (pinfunction "11_11") (pintype "passive"))
      (node (ref "JP1") (pin "13") (pinfunction "13_13") (pintype "passive"))
      (node (ref "JP1") (pin "15") (pinfunction "15_15") (pintype "passive"))
      (node (ref "JP1") (pin "3") (pinfunction "3_3") (pintype "passive"))
      (node (ref "JP1") (pin "5") (pinfunction "5_5") (pintype "passive"))
      (node (ref "JP1") (pin "7") (pinfunction "7_7") (pintype "passive"))
      (node (ref "JP1") (pin "9") (pinfunction "9_9") (pintype "passive"))
      (node (ref "R1") (pin "2") (pinfunction "2_2") (pintype "passive"))
      (node (ref "R29") (pin "1") (pinfunction "1_1") (pintype "passive"))
      (node (ref "SW1") (pin "1") (pinfunction "1_1") (pintype "passive"))
      (node (ref "U$10") (pin "P$2") (pinfunction "2_P$2") (pintype "bidirectional"))
      (node (ref "U$11") (pin "P$2") (pinfunction "2_P$2") (pintype "bidirectional"))
      (node (ref "U$13") (pin "P$2") (pinfunction "2_P$2") (pintype "bidirectional"))
      (node (ref "U$16") (pin "P$2") (pinfunction "2_P$2") (pintype "bidirectional"))
      (node (ref "U$18") (pin "P$2") (pinfunction "2_P$2") (pintype "bidirectional"))
      (node (ref "U$20") (pin "P$2") (pinfunction "2_P$2") (pintype "bidirectional"))
      (node (ref "U$23") (pin "P$2") (pinfunction "2_P$2") (pintype "bidirectional"))
      (node (ref "U$24") (pin "P$2") (pinfunction "2_P$2") (pintype "bidirectional"))
      (node (ref "U$8") (pin "1") (pinfunction "GND_1") (pintype "power_in"))
      (node (ref "WATER_LEVEL") (pin "2") (pinfunction "2_2") (pintype "passive"))
      (node (ref "X1") (pin "1") (pinfunction "1_1") (pintype "passive"))
      (node (ref "X1") (pin "2") (pinfunction "2_2") (pintype "passive"))
    )
    (net (code "50") (name "Net-(LED1-PadC)") (class "Default")
      (node (ref "LED1") (pin "C") (pinfunction "C_C") (pintype "passive"))
      (node (ref "R29") (pin "2") (pinfunction "2_2") (pintype "passive"))
    )
    (net (code "51") (name "Net-(Q1-G)") (class "Default")
      (node (ref "Q1") (pin "1") (pinfunction "G_1") (pintype "passive"))
      (node (ref "R18") (pin "1") (pinfunction "1_1") (pintype "passive"))
      (node (ref "R20") (pin "1") (pinfunction "1_1") (pintype "passive"))
    )
    (net (code "52") (name "Net-(Q2-G)") (class "Default")
      (node (ref "Q2") (pin "1") (pinfunction "G_1") (pintype "passive"))
      (node (ref "R2") (pin "2") (pinfunction "2_2") (pintype "passive"))
      (node (ref "R21") (pin "2") (pinfunction "2_2") (pintype "passive"))
    )
    (net (code "53") (name "Net-(Q3-G)") (class "Default")
      (node (ref "Q3") (pin "1") (pinfunction "G_1") (pintype "passive"))
      (node (ref "R22") (pin "2") (pinfunction "2_2") (pintype "passive"))
      (node (ref "R3") (pin "2") (pinfunction "2_2") (pintype "passive"))
    )
    (net (code "54") (name "Net-(Q4-G)") (class "Default")
      (node (ref "Q4") (pin "1") (pinfunction "G_1") (pintype "passive"))
      (node (ref "R23") (pin "2") (pinfunction "2_2") (pintype "passive"))
      (node (ref "R4") (pin "2") (pinfunction "2_2") (pintype "passive"))
    )
    (net (code "55") (name "Net-(Q5-G)") (class "Default")
      (node (ref "Q5") (pin "1") (pinfunction "G_1") (pintype "passive"))
      (node (ref "R24") (pin "2") (pinfunction "2_2") (pintype "passive"))
      (node (ref "R5") (pin "2") (pinfunction "2_2") (pintype "passive"))
    )
    (net (code "56") (name "Net-(Q6-G)") (class "Default")
      (node (ref "Q6") (pin "1") (pinfunction "G_1") (pintype "passive"))
      (node (ref "R25") (pin "2") (pinfunction "2_2") (pintype "passive"))
      (node (ref "R6") (pin "2") (pinfunction "2_2") (pintype "passive"))
    )
    (net (code "57") (name "Net-(Q7-G)") (class "Default")
      (node (ref "Q7") (pin "1") (pinfunction "G_1") (pintype "passive"))
      (node (ref "R26") (pin "2") (pinfunction "2_2") (pintype "passive"))
      (node (ref "R7") (pin "2") (pinfunction "2_2") (pintype "passive"))
    )
    (net (code "58") (name "Net-(Q8-G)") (class "Default")
      (node (ref "Q8") (pin "1") (pinfunction "G_1") (pintype "passive"))
      (node (ref "R27") (pin "2") (pinfunction "2_2") (pintype "passive"))
      (node (ref "R8") (pin "2") (pinfunction "2_2") (pintype "passive"))
    )
    (net (code "59") (name "Net-(Q9-G)") (class "Default")
      (node (ref "Q9") (pin "1") (pinfunction "G_1") (pintype "passive"))
      (node (ref "R19") (pin "2") (pinfunction "2_2") (pintype "passive"))
      (node (ref "R28") (pin "2") (pinfunction "2_2") (pintype "passive"))
    )
    (net (code "60") (name "Net-(U$10-1)") (class "Default")
      (node (ref "R17") (pin "2") (pinfunction "2_2") (pintype "passive"))
      (node (ref "U$10") (pin "P$1") (pinfunction "1_P$1") (pintype "bidirectional"))
    )
    (net (code "61") (name "Net-(U$10-3)") (class "Default")
      (node (ref "R21") (pin "1") (pinfunction "1_1") (pintype "passive"))
      (node (ref "U$10") (pin "P$3") (pinfunction "3_P$3") (pintype "bidirectional"))
    )
    (net (code "62") (name "Net-(U$11-1)") (class "Default")
      (node (ref "R31") (pin "2") (pinfunction "2_2") (pintype "passive"))
      (node (ref "U$11") (pin "P$1") (pinfunction "1_P$1") (pintype "bidirectional"))
    )
    (net (code "63") (name "Net-(U$11-3)") (class "Default")
      (node (ref "R22") (pin "1") (pinfunction "1_1") (pintype "passive"))
      (node (ref "U$11") (pin "P$3") (pinfunction "3_P$3") (pintype "bidirectional"))
    )
    (net (code "64") (name "Net-(U$13-1)") (class "Default")
      (node (ref "R32") (pin "2") (pinfunction "2_2") (pintype "passive"))
      (node (ref "U$13") (pin "P$1") (pinfunction "1_P$1") (pintype "bidirectional"))
    )
    (net (code "65") (name "Net-(U$13-3)") (class "Default")
      (node (ref "R23") (pin "1") (pinfunction "1_1") (pintype "passive"))
      (node (ref "U$13") (pin "P$3") (pinfunction "3_P$3") (pintype "bidirectional"))
    )
    (net (code "66") (name "Net-(U$16-1)") (class "Default")
      (node (ref "R33") (pin "2") (pinfunction "2_2") (pintype "passive"))
      (node (ref "U$16") (pin "P$1") (pinfunction "1_P$1") (pintype "bidirectional"))
    )
    (net (code "67") (name "Net-(U$16-3)") (class "Default")
      (node (ref "R24") (pin "1") (pinfunction "1_1") (pintype "passive"))
      (node (ref "U$16") (pin "P$3") (pinfunction "3_P$3") (pintype "bidirectional"))
    )
    (net (code "68") (name "Net-(U$18-1)") (class "Default")
      (node (ref "R34") (pin "2") (pinfunction "2_2") (pintype "passive"))
      (node (ref "U$18") (pin "P$1") (pinfunction "1_P$1") (pintype "bidirectional"))
    )
    (net (code "69") (name "Net-(U$18-3)") (class "Default")
      (node (ref "R25") (pin "1") (pinfunction "1_1") (pintype "passive"))
      (node (ref "U$18") (pin "P$3") (pinfunction "3_P$3") (pintype "bidirectional"))
    )
    (net (code "70") (name "Net-(U$20-1)") (class "Default")
      (node (ref "R35") (pin "2") (pinfunction "2_2") (pintype "passive"))
      (node (ref "U$20") (pin "P$1") (pinfunction "1_P$1") (pintype "bidirectional"))
    )
    (net (code "71") (name "Net-(U$20-3)") (class "Default")
      (node (ref "R26") (pin "1") (pinfunction "1_1") (pintype "passive"))
      (node (ref "U$20") (pin "P$3") (pinfunction "3_P$3") (pintype "bidirectional"))
    )
    (net (code "72") (name "Net-(U$23-1)") (class "Default")
      (node (ref "R36") (pin "2") (pinfunction "2_2") (pintype "passive"))
      (node (ref "U$23") (pin "P$1") (pinfunction "1_P$1") (pintype "bidirectional"))
    )
    (net (code "73") (name "Net-(U$23-3)") (class "Default")
      (node (ref "R27") (pin "1") (pinfunction "1_1") (pintype "passive"))
      (node (ref "U$23") (pin "P$3") (pinfunction "3_P$3") (pintype "bidirectional"))
    )
    (net (code "74") (name "Net-(U$24-1)") (class "Default")
      (node (ref "R37") (pin "2") (pinfunction "2_2") (pintype "passive"))
      (node (ref "U$24") (pin "P$1") (pinfunction "1_P$1") (pintype "bidirectional"))
    )
    (net (code "75") (name "Net-(U$24-3)") (class "Default")
      (node (ref "R28") (pin "1") (pinfunction "1_1") (pintype "passive"))
      (node (ref "U$24") (pin "P$3") (pinfunction "3_P$3") (pintype "bidirectional"))
    )
    (net (code "76") (name "unconnected-(IC1-PB2-Pad20)") (class "Default")
      (node (ref "IC1") (pin "20") (pinfunction "PB2_20") (pintype "bidirectional"))
    )
    (net (code "77") (name "unconnected-(IC1-PC13-TAMPER-RTC-Pad2)") (class "Default")
      (node (ref "IC1") (pin "2") (pinfunction "PC13-TAMPER-RTC_2") (pintype "bidirectional"))
    )
    (net (code "78") (name "unconnected-(IC1-PC14-0SC32_IN-Pad3)") (class "Default")
      (node (ref "IC1") (pin "3") (pinfunction "PC14-0SC32_IN_3") (pintype "bidirectional"))
    )
    (net (code "79") (name "unconnected-(IC1-PC15-OSC32_OUT-Pad4)") (class "Default")
      (node (ref "IC1") (pin "4") (pinfunction "PC15-OSC32_OUT_4") (pintype "bidirectional"))
    )
    (net (code "80") (name "unconnected-(IC1-PD0-OSC_IN-Pad5)") (class "Default")
      (node (ref "IC1") (pin "5") (pinfunction "PD0-OSC_IN_5") (pintype "bidirectional"))
    )
    (net (code "81") (name "unconnected-(IC1-PD1-OSC_OUT-Pad6)") (class "Default")
      (node (ref "IC1") (pin "6") (pinfunction "PD1-OSC_OUT_6") (pintype "bidirectional"))
    )
    (net (code "82") (name "unconnected-(SW1-Pad2)") (class "Default")
      (node (ref "SW1") (pin "2") (pinfunction "2_2") (pintype "passive"))
    )
    (net (code "83") (name "unconnected-(SW1-Pad4)") (class "Default")
      (node (ref "SW1") (pin "4") (pinfunction "4_4") (pintype "passive"))
    )
  )
)
